# nRF52810_Beacon.net
KiCad netlist of a schematic drawn in EAGLE
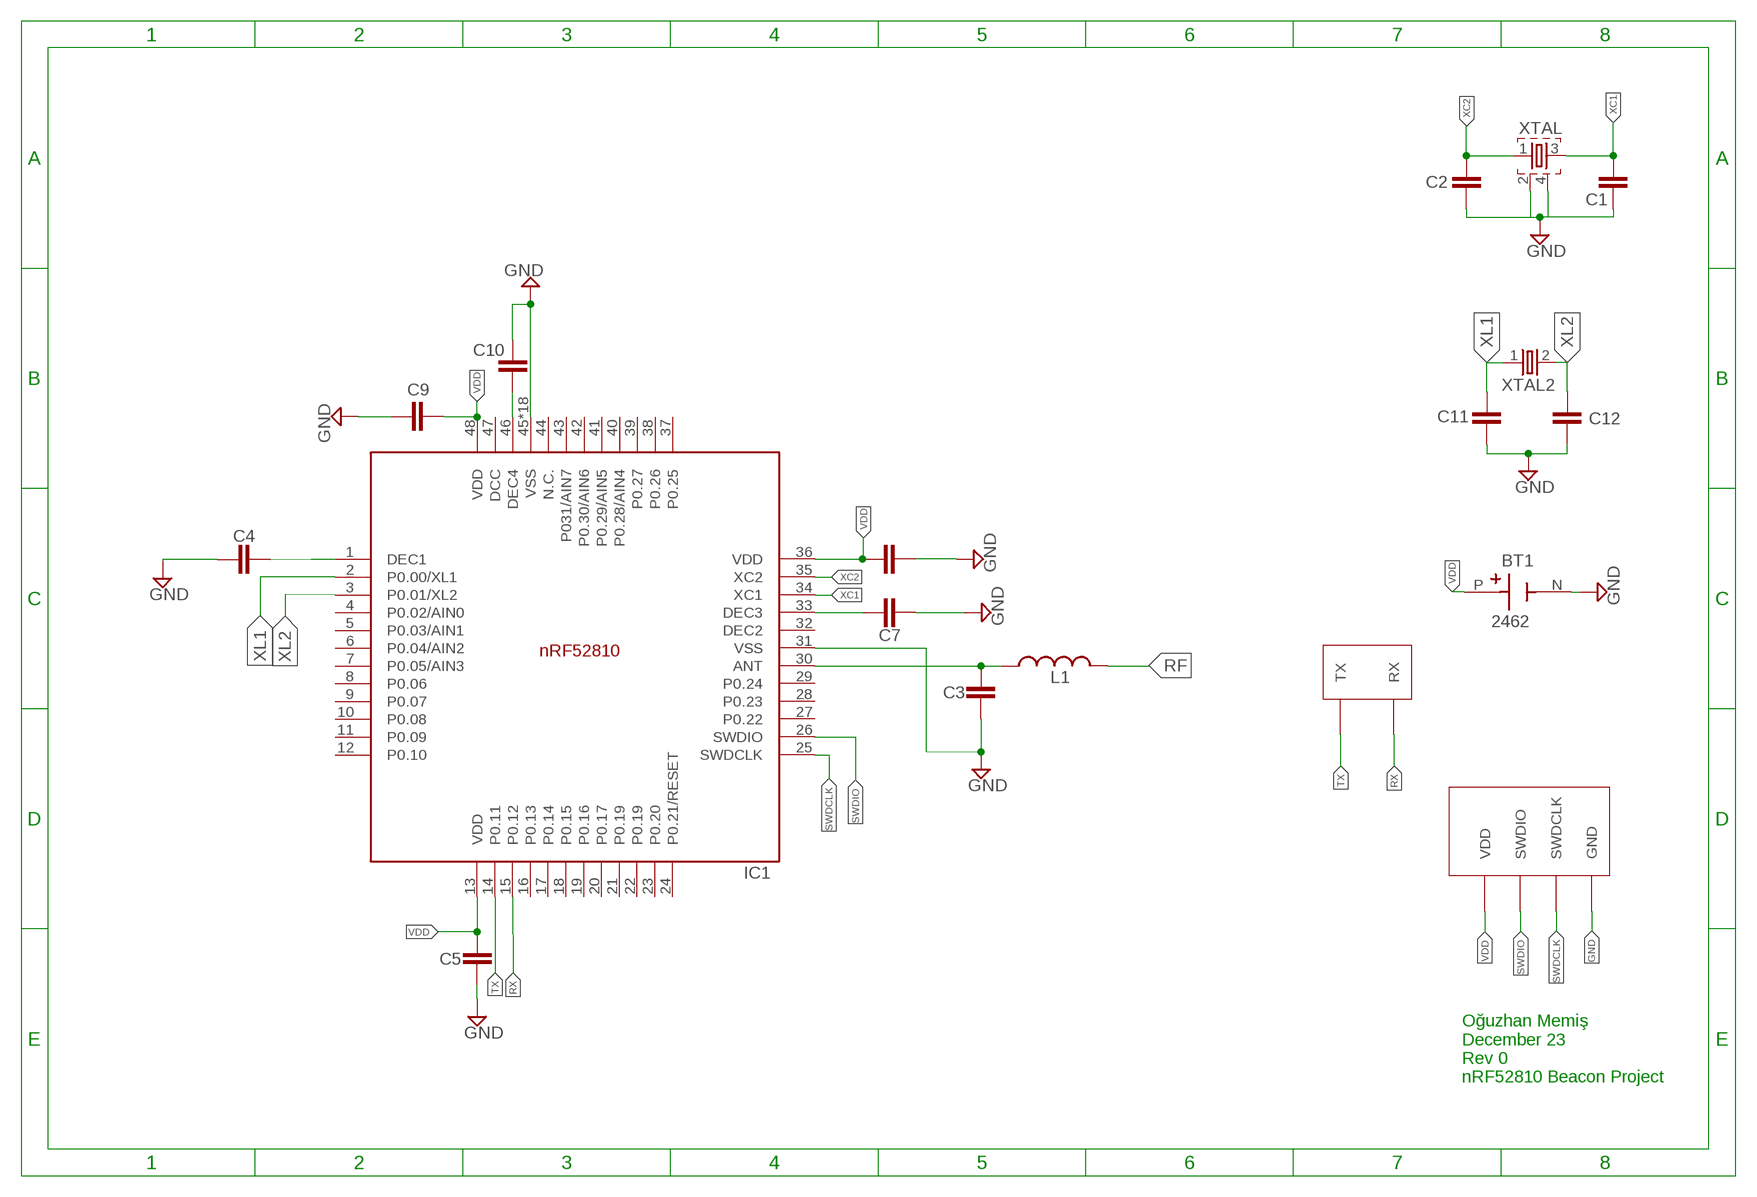
[diagram p0: schematic, sheet 1]

(export (version "E")
  (design (tool "Eeschema 10.0.6"))
  (components
    (comp (ref "BT1")
      (value "2462")
      (footprint "eagle-import:BAT_2462")
      (fields (field (name "MF") "Keystone"))
      (libsource (lib "eagle-import") (part "2462"))
    )
    (comp (ref "C1")
      (value "12pF")
      (footprint "eagle-import:RESC0402_N")
      (libsource (lib "eagle-import") (part "CAPACITOR_0402_N"))
    )
    (comp (ref "C2")
      (value "12pF")
      (footprint "eagle-import:RESC0402_N")
      (libsource (lib "eagle-import") (part "CAPACITOR_0402_N"))
    )
    (comp (ref "C3")
      (value "0.8pF")
      (footprint "eagle-import:RESC0402_N")
      (libsource (lib "eagle-import") (part "CAPACITOR_0402_N"))
    )
    (comp (ref "C4")
      (value "100nF")
      (footprint "eagle-import:RESC0402_N")
      (libsource (lib "eagle-import") (part "CAPACITOR_0402_N"))
    )
    (comp (ref "C5")
      (value "100nF")
      (footprint "eagle-import:RESC0402_N")
      (libsource (lib "eagle-import") (part "CAPACITOR_0402_N"))
    )
    (comp (ref "C7")
      (value "100pF")
      (footprint "eagle-import:RESC0402_N")
      (libsource (lib "eagle-import") (part "CAPACITOR_0402_N"))
    )
    (comp (ref "C8")
      (value "100nF")
      (footprint "eagle-import:RESC0402_N")
      (libsource (lib "eagle-import") (part "CAPACITOR_0402_N"))
    )
    (comp (ref "C9")
      (value "4.7uF")
      (footprint "eagle-import:RESC0603_N")
      (libsource (lib "eagle-import") (part "CAPACITOR_0603_N"))
    )
    (comp (ref "C10")
      (value "1uF")
      (footprint "eagle-import:RESC0603_N")
      (libsource (lib "eagle-import") (part "CAPACITOR_0603_N"))
    )
    (comp (ref "C11")
      (value "12pF")
      (footprint "eagle-import:RESC0402_N")
      (libsource (lib "eagle-import") (part "CAPACITOR_0402_N"))
    )
    (comp (ref "C12")
      (value "12pF")
      (footprint "eagle-import:RESC0402_N")
      (libsource (lib "eagle-import") (part "CAPACITOR_0402_N"))
    )
    (comp (ref "IC1")
      (value "NRF52810_QF48")
      (footprint "eagle-import:QFN40P600X600X90-48_N")
      (libsource (lib "eagle-import") (part "NRF52810_QF48"))
    )
    (comp (ref "L1")
      (value "3.9nF")
      (footprint "eagle-import:RESC0402_N")
      (libsource (lib "eagle-import") (part "INDUCTOR_0402_N"))
    )
    (comp (ref "U$1")
      (value "SWD")
      (footprint "eagle-import:SWD")
      (libsource (lib "eagle-import") (part "SWD"))
    )
    (comp (ref "U$2")
      (value "UART")
      (footprint "eagle-import:UART")
      (libsource (lib "eagle-import") (part "UART"))
    )
    (comp (ref "XTAL")
      (value "32MHz SMD2016")
      (footprint "eagle-import:BT-XTAL_2016_N")
      (libsource (lib "eagle-import") (part "XTAL_32MHZ"))
    )
    (comp (ref "XTAL2")
      (value "32KHz")
      (footprint "eagle-import:XTAL_3215_N")
      (libsource (lib "eagle-import") (part "XTAL_32KHZ"))
    )
  )
  (nets
    (net (code "1") (name "GND") (class "Default")
      (node (ref "BT1") (pin "N") (pinfunction "NEG_N") (pintype "passive"))
      (node (ref "C1") (pin "1") (pinfunction "1_1") (pintype "passive"))
      (node (ref "C10") (pin "2") (pinfunction "2_2") (pintype "passive"))
      (node (ref "C11") (pin "1") (pinfunction "1_1") (pintype "passive"))
      (node (ref "C12") (pin "1") (pinfunction "1_1") (pintype "passive"))
      (node (ref "C2") (pin "1") (pinfunction "1_1") (pintype "passive"))
      (node (ref "C3") (pin "2") (pinfunction "2_2") (pintype "passive"))
      (node (ref "C4") (pin "1") (pinfunction "1_1") (pintype "passive"))
      (node (ref "C5") (pin "2") (pinfunction "2_2") (pintype "passive"))
      (node (ref "C7") (pin "2") (pinfunction "2_2") (pintype "passive"))
      (node (ref "C8") (pin "2") (pinfunction "2_2") (pintype "passive"))
      (node (ref "C9") (pin "1") (pinfunction "1_1") (pintype "passive"))
      (node (ref "IC1") (pin "31") (pinfunction "VSS_31") (pintype "bidirectional"))
      (node (ref "IC1") (pin "45") (pinfunction "VSS_45") (pintype "bidirectional"))
      (node (ref "IC1") (pin "PAD") (pinfunction "VSS_PAD") (pintype "bidirectional"))
      (node (ref "IC1") (pin "PAD@VIA01") (pinfunction "VSS_PAD@VIA01") (pintype "bidirectional"))
      (node (ref "IC1") (pin "PAD@VIA02") (pinfunction "VSS_PAD@VIA02") (pintype "bidirectional"))
      (node (ref "IC1") (pin "PAD@VIA03") (pinfunction "VSS_PAD@VIA03") (pintype "bidirectional"))
      (node (ref "IC1") (pin "PAD@VIA04") (pinfunction "VSS_PAD@VIA04") (pintype "bidirectional"))
      (node (ref "IC1") (pin "PAD@VIA05") (pinfunction "VSS_PAD@VIA05") (pintype "bidirectional"))
      (node (ref "IC1") (pin "PAD@VIA06") (pinfunction "VSS_PAD@VIA06") (pintype "bidirectional"))
      (node (ref "IC1") (pin "PAD@VIA07") (pinfunction "VSS_PAD@VIA07") (pintype "bidirectional"))
      (node (ref "IC1") (pin "PAD@VIA08") (pinfunction "VSS_PAD@VIA08") (pintype "bidirectional"))
      (node (ref "IC1") (pin "PAD@VIA09") (pinfunction "VSS_PAD@VIA09") (pintype "bidirectional"))
      (node (ref "IC1") (pin "PAD@VIA10") (pinfunction "VSS_PAD@VIA10") (pintype "bidirectional"))
      (node (ref "IC1") (pin "PAD@VIA11") (pinfunction "VSS_PAD@VIA11") (pintype "bidirectional"))
      (node (ref "IC1") (pin "PAD@VIA12") (pinfunction "VSS_PAD@VIA12") (pintype "bidirectional"))
      (node (ref "IC1") (pin "PAD@VIA13") (pinfunction "VSS_PAD@VIA13") (pintype "bidirectional"))
      (node (ref "IC1") (pin "PAD@VIA14") (pinfunction "VSS_PAD@VIA14") (pintype "bidirectional"))
      (node (ref "IC1") (pin "PAD@VIA15") (pinfunction "VSS_PAD@VIA15") (pintype "bidirectional"))
      (node (ref "IC1") (pin "PAD@VIA16") (pinfunction "VSS_PAD@VIA16") (pintype "bidirectional"))
      (node (ref "U$1") (pin "GND") (pinfunction "GND_GND") (pintype "bidirectional"))
      (node (ref "XTAL") (pin "2") (pinfunction "2_2") (pintype "passive"))
      (node (ref "XTAL") (pin "4") (pinfunction "4_4") (pintype "passive"))
    )
    (net (code "2") (name "Net-(IC1-ANT)") (class "Default")
      (node (ref "C3") (pin "1") (pinfunction "1_1") (pintype "passive"))
      (node (ref "IC1") (pin "30") (pinfunction "ANT_30") (pintype "bidirectional"))
      (node (ref "L1") (pin "1") (pinfunction "1_1") (pintype "passive"))
    )
    (net (code "3") (name "Net-(IC1-DEC1)") (class "Default")
      (node (ref "C4") (pin "2") (pinfunction "2_2") (pintype "passive"))
      (node (ref "IC1") (pin "1") (pinfunction "DEC1_1") (pintype "bidirectional"))
    )
    (net (code "4") (name "Net-(IC1-DEC3)") (class "Default")
      (node (ref "C7") (pin "1") (pinfunction "1_1") (pintype "passive"))
      (node (ref "IC1") (pin "33") (pinfunction "DEC3_33") (pintype "bidirectional"))
    )
    (net (code "5") (name "Net-(IC1-DEC4)") (class "Default")
      (node (ref "C10") (pin "1") (pinfunction "1_1") (pintype "passive"))
      (node (ref "IC1") (pin "46") (pinfunction "DEC4_46") (pintype "bidirectional"))
    )
    (net (code "6") (name "RF") (class "Default")
      (node (ref "L1") (pin "2") (pinfunction "2_2") (pintype "passive"))
    )
    (net (code "7") (name "RX") (class "Default")
      (node (ref "IC1") (pin "15") (pinfunction "P0.12_15") (pintype "bidirectional"))
      (node (ref "U$2") (pin "RX") (pinfunction "RX_RX") (pintype "bidirectional"))
    )
    (net (code "8") (name "SWDCLK") (class "Default")
      (node (ref "IC1") (pin "25") (pinfunction "SWDCLK_25") (pintype "bidirectional"))
      (node (ref "U$1") (pin "SWDCLK") (pinfunction "SWDCLK_SWDCLK") (pintype "bidirectional"))
    )
    (net (code "9") (name "SWDIO") (class "Default")
      (node (ref "IC1") (pin "26") (pinfunction "SWDIO_26") (pintype "bidirectional"))
      (node (ref "U$1") (pin "SWDIO") (pinfunction "SWDIO_SWDIO") (pintype "bidirectional"))
    )
    (net (code "10") (name "TX") (class "Default")
      (node (ref "IC1") (pin "14") (pinfunction "P0.11_14") (pintype "bidirectional"))
      (node (ref "U$2") (pin "TX") (pinfunction "TX_TX") (pintype "bidirectional"))
    )
    (net (code "11") (name "VDD") (class "Default")
      (node (ref "BT1") (pin "P") (pinfunction "POS_P") (pintype "passive"))
      (node (ref "C5") (pin "1") (pinfunction "1_1") (pintype "passive"))
      (node (ref "C8") (pin "1") (pinfunction "1_1") (pintype "passive"))
      (node (ref "C9") (pin "2") (pinfunction "2_2") (pintype "passive"))
      (node (ref "IC1") (pin "13") (pinfunction "VDD_13") (pintype "bidirectional"))
      (node (ref "IC1") (pin "36") (pinfunction "VDD_36") (pintype "bidirectional"))
      (node (ref "IC1") (pin "48") (pinfunction "VDD_48") (pintype "bidirectional"))
      (node (ref "U$1") (pin "VDD") (pinfunction "VDD_VDD") (pintype "bidirectional"))
    )
    (net (code "12") (name "XC1") (class "Default")
      (node (ref "C1") (pin "2") (pinfunction "2_2") (pintype "passive"))
      (node (ref "IC1") (pin "34") (pinfunction "XC1_34") (pintype "bidirectional"))
      (node (ref "XTAL") (pin "3") (pinfunction "3_3") (pintype "passive"))
    )
    (net (code "13") (name "XC2") (class "Default")
      (node (ref "C2") (pin "2") (pinfunction "2_2") (pintype "passive"))
      (node (ref "IC1") (pin "35") (pinfunction "XC2_35") (pintype "bidirectional"))
      (node (ref "XTAL") (pin "1") (pinfunction "1_1") (pintype "passive"))
    )
    (net (code "14") (name "XL1") (class "Default")
      (node (ref "C11") (pin "2") (pinfunction "2_2") (pintype "passive"))
      (node (ref "IC1") (pin "2") (pinfunction "P0.00/XL1_2") (pintype "bidirectional"))
      (node (ref "XTAL2") (pin "1") (pinfunction "1_1") (pintype "passive"))
    )
    (net (code "15") (name "XL2") (class "Default")
      (node (ref "C12") (pin "2") (pinfunction "2_2") (pintype "passive"))
      (node (ref "IC1") (pin "3") (pinfunction "P0.01/XL2_3") (pintype "bidirectional"))
      (node (ref "XTAL2") (pin "2") (pinfunction "2_2") (pintype "passive"))
    )
    (net (code "16") (name "unconnected-(IC1-DCC-Pad47)") (class "Default")
      (node (ref "IC1") (pin "47") (pinfunction "DCC_47") (pintype "bidirectional"))
    )
    (net (code "17") (name "unconnected-(IC1-DEC2-Pad32)") (class "Default")
      (node (ref "IC1") (pin "32") (pinfunction "DEC2_32") (pintype "bidirectional"))
    )
    (net (code "18") (name "unconnected-(IC1-N.C.-Pad44)") (class "Default")
      (node (ref "IC1") (pin "44") (pinfunction "N.C._44") (pintype "bidirectional"))
    )
    (net (code "19") (name "unconnected-(IC1-P0.02{slash}AIN0-Pad4)") (class "Default")
      (node (ref "IC1") (pin "4") (pinfunction "P0.02/AIN0_4") (pintype "bidirectional"))
    )
    (net (code "20") (name "unconnected-(IC1-P0.03{slash}AIN1-Pad5)") (class "Default")
      (node (ref "IC1") (pin "5") (pinfunction "P0.03/AIN1_5") (pintype "bidirectional"))
    )
    (net (code "21") (name "unconnected-(IC1-P0.04{slash}AIN2-Pad6)") (class "Default")
      (node (ref "IC1") (pin "6") (pinfunction "P0.04/AIN2_6") (pintype "bidirectional"))
    )
    (net (code "22") (name "unconnected-(IC1-P0.05{slash}AIN3-Pad7)") (class "Default")
      (node (ref "IC1") (pin "7") (pinfunction "P0.05/AIN3_7") (pintype "bidirectional"))
    )
    (net (code "23") (name "unconnected-(IC1-P0.06-Pad8)") (class "Default")
      (node (ref "IC1") (pin "8") (pinfunction "P0.06_8") (pintype "bidirectional"))
    )
    (net (code "24") (name "unconnected-(IC1-P0.07-Pad9)") (class "Default")
      (node (ref "IC1") (pin "9") (pinfunction "P0.07_9") (pintype "bidirectional"))
    )
    (net (code "25") (name "unconnected-(IC1-P0.08-Pad10)") (class "Default")
      (node (ref "IC1") (pin "10") (pinfunction "P0.08_10") (pintype "bidirectional"))
    )
    (net (code "26") (name "unconnected-(IC1-P0.09-Pad11)") (class "Default")
      (node (ref "IC1") (pin "11") (pinfunction "P0.09_11") (pintype "bidirectional"))
    )
    (net (code "27") (name "unconnected-(IC1-P0.10-Pad12)") (class "Default")
      (node (ref "IC1") (pin "12") (pinfunction "P0.10_12") (pintype "bidirectional"))
    )
    (net (code "28") (name "unconnected-(IC1-P0.13-Pad16)") (class "Default")
      (node (ref "IC1") (pin "16") (pinfunction "P0.13_16") (pintype "bidirectional"))
    )
    (net (code "29") (name "unconnected-(IC1-P0.14-Pad17)") (class "Default")
      (node (ref "IC1") (pin "17") (pinfunction "P0.14_17") (pintype "bidirectional"))
    )
    (net (code "30") (name "unconnected-(IC1-P0.15-Pad18)") (class "Default")
      (node (ref "IC1") (pin "18") (pinfunction "P0.15_18") (pintype "bidirectional"))
    )
    (net (code "31") (name "unconnected-(IC1-P0.16-Pad19)") (class "Default")
      (node (ref "IC1") (pin "19") (pinfunction "P0.16_19") (pintype "bidirectional"))
    )
    (net (code "32") (name "unconnected-(IC1-P0.17-Pad20)") (class "Default")
      (node (ref "IC1") (pin "20") (pinfunction "P0.17_20") (pintype "bidirectional"))
    )
    (net (code "33") (name "unconnected-(IC1-P0.19-Pad21)") (class "Default")
      (node (ref "IC1") (pin "21") (pinfunction "P0.19_21") (pintype "bidirectional"))
    )
    (net (code "34") (name "unconnected-(IC1-P0.19-Pad22)") (class "Default")
      (node (ref "IC1") (pin "22") (pinfunction "P0.19_22") (pintype "bidirectional"))
    )
    (net (code "35") (name "unconnected-(IC1-P0.20-Pad23)") (class "Default")
      (node (ref "IC1") (pin "23") (pinfunction "P0.20_23") (pintype "bidirectional"))
    )
    (net (code "36") (name "unconnected-(IC1-P0.21{slash}RESET-Pad24)") (class "Default")
      (node (ref "IC1") (pin "24") (pinfunction "P0.21/RESET_24") (pintype "bidirectional"))
    )
    (net (code "37") (name "unconnected-(IC1-P0.22-Pad27)") (class "Default")
      (node (ref "IC1") (pin "27") (pinfunction "P0.22_27") (pintype "bidirectional"))
    )
    (net (code "38") (name "unconnected-(IC1-P0.23-Pad28)") (class "Default")
      (node (ref "IC1") (pin "28") (pinfunction "P0.23_28") (pintype "bidirectional"))
    )
    (net (code "39") (name "unconnected-(IC1-P0.24-Pad29)") (class "Default")
      (node (ref "IC1") (pin "29") (pinfunction "P0.24_29") (pintype "bidirectional"))
    )
    (net (code "40") (name "unconnected-(IC1-P0.25-Pad37)") (class "Default")
      (node (ref "IC1") (pin "37") (pinfunction "P0.25_37") (pintype "bidirectional"))
    )
    (net (code "41") (name "unconnected-(IC1-P0.26-Pad38)") (class "Default")
      (node (ref "IC1") (pin "38") (pinfunction "P0.26_38") (pintype "bidirectional"))
    )
    (net (code "42") (name "unconnected-(IC1-P0.27-Pad39)") (class "Default")
      (node (ref "IC1") (pin "39") (pinfunction "P0.27_39") (pintype "bidirectional"))
    )
    (net (code "43") (name "unconnected-(IC1-P0.28{slash}AIN4-Pad40)") (class "Default")
      (node (ref "IC1") (pin "40") (pinfunction "P0.28/AIN4_40") (pintype "bidirectional"))
    )
    (net (code "44") (name "unconnected-(IC1-P0.29{slash}AIN5-Pad41)") (class "Default")
      (node (ref "IC1") (pin "41") (pinfunction "P0.29/AIN5_41") (pintype "bidirectional"))
    )
    (net (code "45") (name "unconnected-(IC1-P0.30{slash}AIN6-Pad42)") (class "Default")
      (node (ref "IC1") (pin "42") (pinfunction "P0.30/AIN6_42") (pintype "bidirectional"))
    )
    (net (code "46") (name "unconnected-(IC1-P031{slash}AIN7-Pad43)") (class "Default")
      (node (ref "IC1") (pin "43") (pinfunction "P031/AIN7_43") (pintype "bidirectional"))
    )
  )
)
